# RibbonCable.net
KiCad netlist of a schematic drawn in Altium Designer
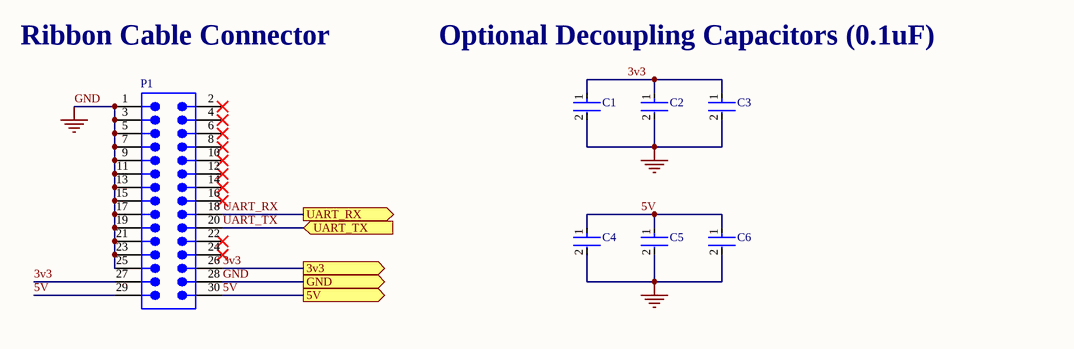
[diagram p0: RibbonCable.SchDoc]

(export (version "E")
  (design (tool "Eeschema 10.0.6"))
  (components
    (comp (ref "C1")
      (value "GRM033C71C104KE14D")
      (footprint "FP-GRM033-0_03-MFG")
      (description "Chip Multilayer Ceramic Capacitors for General Purpose, 0201, 0.10uF, X7S, 22%, 10%, 16V")
      (fields (field (name "TOLERANCE") "10%"))
      (libsource (lib "Altium Content Vault") (part "b4654b650e69147ec39a6b967a45e02"))
    )
    (comp (ref "C2")
      (value "GRM033C71C104KE14D")
      (footprint "FP-GRM033-0_03-MFG")
      (description "Chip Multilayer Ceramic Capacitors for General Purpose, 0201, 0.10uF, X7S, 22%, 10%, 16V")
      (fields (field (name "TOLERANCE") "10%"))
      (libsource (lib "Altium Content Vault") (part "b4654b650e69147ec39a6b967a45e02"))
    )
    (comp (ref "C3")
      (value "GRM033C71C104KE14D")
      (footprint "FP-GRM033-0_03-MFG")
      (description "Chip Multilayer Ceramic Capacitors for General Purpose, 0201, 0.10uF, X7S, 22%, 10%, 16V")
      (fields (field (name "TOLERANCE") "10%"))
      (libsource (lib "Altium Content Vault") (part "b4654b650e69147ec39a6b967a45e02"))
    )
    (comp (ref "C4")
      (value "GRM033C71C104KE14D")
      (footprint "FP-GRM033-0_03-MFG")
      (description "Chip Multilayer Ceramic Capacitors for General Purpose, 0201, 0.10uF, X7S, 22%, 10%, 16V")
      (fields (field (name "TOLERANCE") "10%"))
      (libsource (lib "Altium Content Vault") (part "b4654b650e69147ec39a6b967a45e02"))
    )
    (comp (ref "C5")
      (value "GRM033C71C104KE14D")
      (footprint "FP-GRM033-0_03-MFG")
      (description "Chip Multilayer Ceramic Capacitors for General Purpose, 0201, 0.10uF, X7S, 22%, 10%, 16V")
      (fields (field (name "TOLERANCE") "10%"))
      (libsource (lib "Altium Content Vault") (part "b4654b650e69147ec39a6b967a45e02"))
    )
    (comp (ref "C6")
      (value "GRM033C71C104KE14D")
      (footprint "FP-GRM033-0_03-MFG")
      (description "Chip Multilayer Ceramic Capacitors for General Purpose, 0201, 0.10uF, X7S, 22%, 10%, 16V")
      (fields (field (name "TOLERANCE") "10%"))
      (libsource (lib "Altium Content Vault") (part "b4654b650e69147ec39a6b967a45e02"))
    )
    (comp (ref "P1")
      (value "62703021721")
      (footprint "62703021721")
      (description "62703021721 Conn, R/A Header, 30Pos, 2Row, 1.27Mm Rohs Compliant: Yes")
      (libsource (lib "Altium Content Vault") (part "Header_Male_2R_30P"))
    )
  )
  (nets
    (net (code "1") (name "/3v3") (class "Default")
      (node (ref "C1") (pin "1") (pinfunction "1_1") (pintype "passive"))
      (node (ref "C2") (pin "1") (pinfunction "1_1") (pintype "passive"))
      (node (ref "C3") (pin "1") (pinfunction "1_1") (pintype "passive"))
      (node (ref "P1") (pin "26") (pinfunction "26_26") (pintype "passive"))
      (node (ref "P1") (pin "27") (pinfunction "27_27") (pintype "passive"))
    )
    (net (code "2") (name "/5V") (class "Default")
      (node (ref "C4") (pin "1") (pinfunction "1_1") (pintype "passive"))
      (node (ref "C5") (pin "1") (pinfunction "1_1") (pintype "passive"))
      (node (ref "C6") (pin "1") (pinfunction "1_1") (pintype "passive"))
      (node (ref "P1") (pin "29") (pinfunction "29_29") (pintype "passive"))
      (node (ref "P1") (pin "30") (pinfunction "30_30") (pintype "passive"))
    )
    (net (code "3") (name "/UART_RX") (class "Default")
      (node (ref "P1") (pin "18") (pinfunction "18_18") (pintype "passive"))
    )
    (net (code "4") (name "/UART_TX") (class "Default")
      (node (ref "P1") (pin "20") (pinfunction "20_20") (pintype "passive"))
    )
    (net (code "5") (name "GND") (class "Default")
      (node (ref "C1") (pin "2") (pinfunction "2_2") (pintype "passive"))
      (node (ref "C2") (pin "2") (pinfunction "2_2") (pintype "passive"))
      (node (ref "C3") (pin "2") (pinfunction "2_2") (pintype "passive"))
      (node (ref "C4") (pin "2") (pinfunction "2_2") (pintype "passive"))
      (node (ref "C5") (pin "2") (pinfunction "2_2") (pintype "passive"))
      (node (ref "C6") (pin "2") (pinfunction "2_2") (pintype "passive"))
      (node (ref "P1") (pin "1") (pinfunction "1_1") (pintype "passive"))
      (node (ref "P1") (pin "11") (pinfunction "11_11") (pintype "passive"))
      (node (ref "P1") (pin "13") (pinfunction "13_13") (pintype "passive"))
      (node (ref "P1") (pin "15") (pinfunction "15_15") (pintype "passive"))
      (node (ref "P1") (pin "17") (pinfunction "17_17") (pintype "passive"))
      (node (ref "P1") (pin "19") (pinfunction "19_19") (pintype "passive"))
      (node (ref "P1") (pin "21") (pinfunction "21_21") (pintype "passive"))
      (node (ref "P1") (pin "23") (pinfunction "23_23") (pintype "passive"))
      (node (ref "P1") (pin "25") (pinfunction "25_25") (pintype "passive"))
      (node (ref "P1") (pin "28") (pinfunction "28_28") (pintype "passive"))
      (node (ref "P1") (pin "3") (pinfunction "3_3") (pintype "passive"))
      (node (ref "P1") (pin "5") (pinfunction "5_5") (pintype "passive"))
      (node (ref "P1") (pin "7") (pinfunction "7_7") (pintype "passive"))
      (node (ref "P1") (pin "9") (pinfunction "9_9") (pintype "passive"))
    )
    (net (code "6") (name "unconnected-(P1-Pad2)") (class "Default")
      (node (ref "P1") (pin "2") (pinfunction "2_2") (pintype "passive+no_connect"))
    )
    (net (code "7") (name "unconnected-(P1-Pad4)") (class "Default")
      (node (ref "P1") (pin "4") (pinfunction "4_4") (pintype "passive+no_connect"))
    )
    (net (code "8") (name "unconnected-(P1-Pad6)") (class "Default")
      (node (ref "P1") (pin "6") (pinfunction "6_6") (pintype "passive+no_connect"))
    )
    (net (code "9") (name "unconnected-(P1-Pad8)") (class "Default")
      (node (ref "P1") (pin "8") (pinfunction "8_8") (pintype "passive+no_connect"))
    )
    (net (code "10") (name "unconnected-(P1-Pad10)") (class "Default")
      (node (ref "P1") (pin "10") (pinfunction "10_10") (pintype "passive+no_connect"))
    )
    (net (code "11") (name "unconnected-(P1-Pad12)") (class "Default")
      (node (ref "P1") (pin "12") (pinfunction "12_12") (pintype "passive+no_connect"))
    )
    (net (code "12") (name "unconnected-(P1-Pad14)") (class "Default")
      (node (ref "P1") (pin "14") (pinfunction "14_14") (pintype "passive+no_connect"))
    )
    (net (code "13") (name "unconnected-(P1-Pad16)") (class "Default")
      (node (ref "P1") (pin "16") (pinfunction "16_16") (pintype "passive+no_connect"))
    )
    (net (code "14") (name "unconnected-(P1-Pad22)") (class "Default")
      (node (ref "P1") (pin "22") (pinfunction "22_22") (pintype "passive+no_connect"))
    )
    (net (code "15") (name "unconnected-(P1-Pad24)") (class "Default")
      (node (ref "P1") (pin "24") (pinfunction "24_24") (pintype "passive+no_connect"))
    )
  )
)
